# PCIe_LB_bridge.net
KiCad netlist of a schematic drawn in Altium Designer
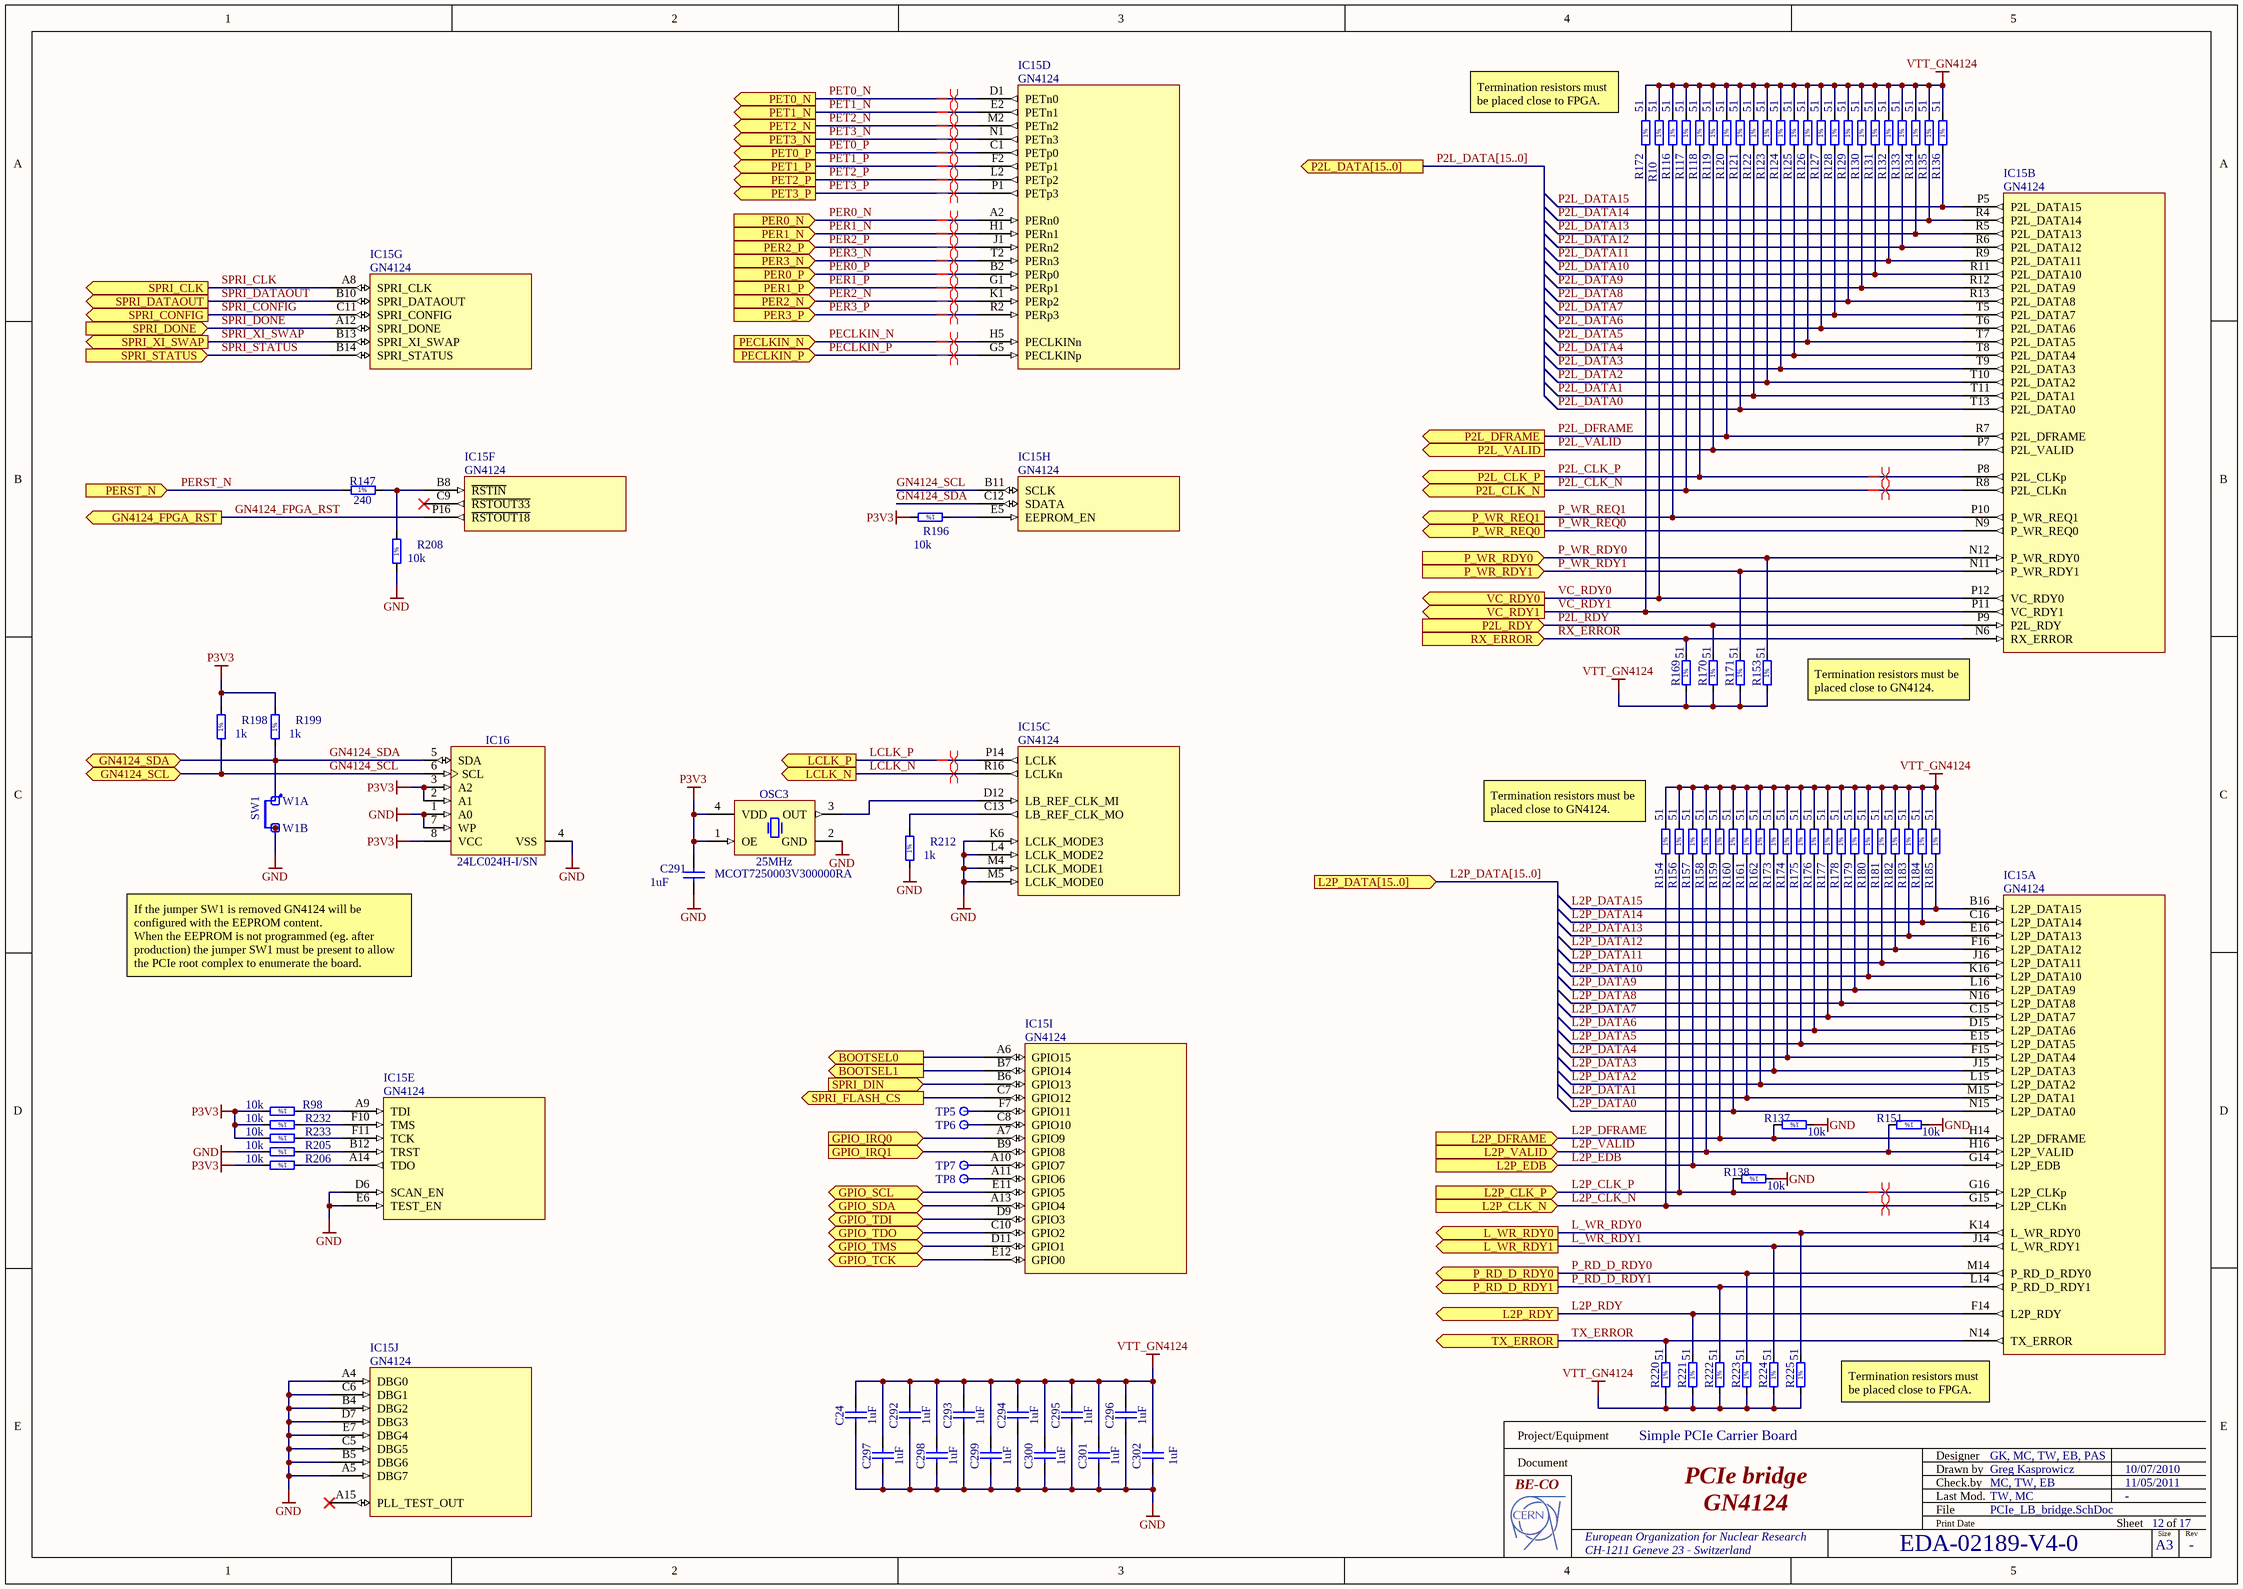
[diagram p0: PCIe_LB_bridge.SchDoc]

(export (version "E")
  (design (tool "Eeschema 10.0.6"))
  (components
    (comp (ref "C24")
      (value "1uF")
      (footprint "CAPC1608X87N")
      (description "Non-polarised capacitor")
      (fields
        (field (name "PART NUMBER") "CC0603_1UF_16V_10%_X7R")
        (field (name "VOLTAGE") "16V")
        (field (name "AUTHOR") "CERN DEM JLC")
      )
      (libsource (lib "Capacitors") (part "Capacitor - non polarized"))
    )
    (comp (ref "C291")
      (value "1uF")
      (footprint "CAPC1608X87N")
      (description "Non-polarised capacitor")
      (fields
        (field (name "PART NUMBER") "CC0603_1UF_16V_10%_X7R")
        (field (name "VOLTAGE") "16V")
        (field (name "AUTHOR") "CERN DEM JLC")
      )
      (libsource (lib "Capacitors") (part "Capacitor - non polarized"))
    )
    (comp (ref "C292")
      (value "1uF")
      (footprint "CAPC1608X87N")
      (description "Non-polarised capacitor")
      (fields
        (field (name "PART NUMBER") "CC0603_1UF_16V_10%_X7R")
        (field (name "VOLTAGE") "16V")
        (field (name "AUTHOR") "CERN DEM JLC")
      )
      (libsource (lib "Capacitors") (part "Capacitor - non polarized"))
    )
    (comp (ref "C293")
      (value "1uF")
      (footprint "CAPC1608X87N")
      (description "Non-polarised capacitor")
      (fields
        (field (name "PART NUMBER") "CC0603_1UF_16V_10%_X7R")
        (field (name "VOLTAGE") "16V")
        (field (name "AUTHOR") "CERN DEM JLC")
      )
      (libsource (lib "Capacitors") (part "Capacitor - non polarized"))
    )
    (comp (ref "C294")
      (value "1uF")
      (footprint "CAPC1608X87N")
      (description "Non-polarised capacitor")
      (fields
        (field (name "PART NUMBER") "CC0603_1UF_16V_10%_X7R")
        (field (name "VOLTAGE") "16V")
        (field (name "AUTHOR") "CERN DEM JLC")
      )
      (libsource (lib "Capacitors") (part "Capacitor - non polarized"))
    )
    (comp (ref "C295")
      (value "1uF")
      (footprint "CAPC1608X87N")
      (description "Non-polarised capacitor")
      (fields
        (field (name "PART NUMBER") "CC0603_1UF_16V_10%_X7R")
        (field (name "VOLTAGE") "16V")
        (field (name "AUTHOR") "CERN DEM JLC")
      )
      (libsource (lib "Capacitors") (part "Capacitor - non polarized"))
    )
    (comp (ref "C296")
      (value "1uF")
      (footprint "CAPC1608X87N")
      (description "Non-polarised capacitor")
      (fields
        (field (name "PART NUMBER") "CC0603_1UF_16V_10%_X7R")
        (field (name "VOLTAGE") "16V")
        (field (name "AUTHOR") "CERN DEM JLC")
      )
      (libsource (lib "Capacitors") (part "Capacitor - non polarized"))
    )
    (comp (ref "C297")
      (value "1uF")
      (footprint "CAPC1608X87N")
      (description "Non-polarised capacitor")
      (fields
        (field (name "PART NUMBER") "CC0603_1UF_16V_10%_X7R")
        (field (name "VOLTAGE") "16V")
        (field (name "AUTHOR") "CERN DEM JLC")
      )
      (libsource (lib "Capacitors") (part "Capacitor - non polarized"))
    )
    (comp (ref "C298")
      (value "1uF")
      (footprint "CAPC1608X87N")
      (description "Non-polarised capacitor")
      (fields
        (field (name "PART NUMBER") "CC0603_1UF_16V_10%_X7R")
        (field (name "VOLTAGE") "16V")
        (field (name "AUTHOR") "CERN DEM JLC")
      )
      (libsource (lib "Capacitors") (part "Capacitor - non polarized"))
    )
    (comp (ref "C299")
      (value "1uF")
      (footprint "CAPC1608X87N")
      (description "Non-polarised capacitor")
      (fields
        (field (name "PART NUMBER") "CC0603_1UF_16V_10%_X7R")
        (field (name "VOLTAGE") "16V")
        (field (name "AUTHOR") "CERN DEM JLC")
      )
      (libsource (lib "Capacitors") (part "Capacitor - non polarized"))
    )
    (comp (ref "C300")
      (value "1uF")
      (footprint "CAPC1608X87N")
      (description "Non-polarised capacitor")
      (fields
        (field (name "PART NUMBER") "CC0603_1UF_16V_10%_X7R")
        (field (name "VOLTAGE") "16V")
        (field (name "AUTHOR") "CERN DEM JLC")
      )
      (libsource (lib "Capacitors") (part "Capacitor - non polarized"))
    )
    (comp (ref "C301")
      (value "1uF")
      (footprint "CAPC1608X87N")
      (description "Non-polarised capacitor")
      (fields
        (field (name "PART NUMBER") "CC0603_1UF_16V_10%_X7R")
        (field (name "VOLTAGE") "16V")
        (field (name "AUTHOR") "CERN DEM JLC")
      )
      (libsource (lib "Capacitors") (part "Capacitor - non polarized"))
    )
    (comp (ref "C302")
      (value "1uF")
      (footprint "CAPC1608X87N")
      (description "Non-polarised capacitor")
      (fields
        (field (name "PART NUMBER") "CC0603_1UF_16V_10%_X7R")
        (field (name "VOLTAGE") "16V")
        (field (name "AUTHOR") "CERN DEM JLC")
      )
      (libsource (lib "Capacitors") (part "Capacitor - non polarized"))
    )
    (comp (ref "IC15")
      (value "GN4124")
      (footprint "BGA256C100P16X16_1700X1700X150")
      (description "x4 Lane PCI Express to Local Bridge")
      (fields (field (name "MANUFACTURER") "GENNUM") (field (name "AUTHOR") "CERN DEM JLC"))
      (libsource (lib "ICs And Semiconductors") (part "GN4124"))
    )
    (comp (ref "IC16")
      (value "24LC024H-I/SN")
      (footprint "SOIC127P600X175-8N")
      (description "2K I2C Serial EEPROM With Half-Array Write Protect")
      (fields (field (name "MANUFACTURER") "MICROCHIP TECHNOLOGY") (field (name "AUTHOR") "CERN DEM JLC"))
      (libsource (lib "ICs And Semiconductors") (part "24LC024H-I/SN"))
    )
    (comp (ref "OSC3")
      (value "25MHz")
      (footprint "OSCSC508P500X700X160-4N")
      (description "Oscillator 4 pins 1=OE 2=GND 3=OUT 4=VDD")
      (fields
        (field (name "PART NUMBER") "OSC_25MHZ_MULTICOMP_MCOT7250003V300000RA")
        (field (name "MANUFACTURER") "MULTICOMP")
        (field (name "MANUFACTURER PART NUMBER") "MCOT7250003V300000RA")
        (field (name "AUTHOR") "CERN DEM JLC")
      )
      (libsource (lib "ICs And Semiconductors") (part "Oscillator 1OE 2GND 3OUT 4VDD"))
    )
    (comp (ref "R10")
      (value "51")
      (footprint "RESC1005X40N")
      (description "Resistor - 1%")
      (fields
        (field (name "PART NUMBER") "R0402_51R_1%_0.0625W_100PPM")
        (field (name "POWER") "0.0625W")
        (field (name "AUTHOR") "CERN DEM JLC")
      )
      (libsource (lib "Resistors") (part "Resistor - 1%"))
    )
    (comp (ref "R98")
      (value "10k")
      (footprint "RESC1608X55N")
      (description "Resistor - 1%")
      (fields
        (field (name "PART NUMBER") "R0603_10K_1%_0.1W_100PPM")
        (field (name "POWER") "0.1W")
        (field (name "AUTHOR") "CERN DEM JLC")
      )
      (libsource (lib "Resistors") (part "Resistor - 1%"))
    )
    (comp (ref "R116")
      (value "51")
      (footprint "RESC1005X40N")
      (description "Resistor - 1%")
      (fields
        (field (name "PART NUMBER") "R0402_51R_1%_0.0625W_100PPM")
        (field (name "POWER") "0.0625W")
        (field (name "AUTHOR") "CERN DEM JLC")
      )
      (libsource (lib "Resistors") (part "Resistor - 1%"))
    )
    (comp (ref "R117")
      (value "51")
      (footprint "RESC1005X40N")
      (description "Resistor - 1%")
      (fields
        (field (name "PART NUMBER") "R0402_51R_1%_0.0625W_100PPM")
        (field (name "POWER") "0.0625W")
        (field (name "AUTHOR") "CERN DEM JLC")
      )
      (libsource (lib "Resistors") (part "Resistor - 1%"))
    )
    (comp (ref "R118")
      (value "51")
      (footprint "RESC1005X40N")
      (description "Resistor - 1%")
      (fields
        (field (name "PART NUMBER") "R0402_51R_1%_0.0625W_100PPM")
        (field (name "POWER") "0.0625W")
        (field (name "AUTHOR") "CERN DEM JLC")
      )
      (libsource (lib "Resistors") (part "Resistor - 1%"))
    )
    (comp (ref "R119")
      (value "51")
      (footprint "RESC1005X40N")
      (description "Resistor - 1%")
      (fields
        (field (name "PART NUMBER") "R0402_51R_1%_0.0625W_100PPM")
        (field (name "POWER") "0.0625W")
        (field (name "AUTHOR") "CERN DEM JLC")
      )
      (libsource (lib "Resistors") (part "Resistor - 1%"))
    )
    (comp (ref "R120")
      (value "51")
      (footprint "RESC1005X40N")
      (description "Resistor - 1%")
      (fields
        (field (name "PART NUMBER") "R0402_51R_1%_0.0625W_100PPM")
        (field (name "POWER") "0.0625W")
        (field (name "AUTHOR") "CERN DEM JLC")
      )
      (libsource (lib "Resistors") (part "Resistor - 1%"))
    )
    (comp (ref "R121")
      (value "51")
      (footprint "RESC1005X40N")
      (description "Resistor - 1%")
      (fields
        (field (name "PART NUMBER") "R0402_51R_1%_0.0625W_100PPM")
        (field (name "POWER") "0.0625W")
        (field (name "AUTHOR") "CERN DEM JLC")
      )
      (libsource (lib "Resistors") (part "Resistor - 1%"))
    )
    (comp (ref "R122")
      (value "51")
      (footprint "RESC1005X40N")
      (description "Resistor - 1%")
      (fields
        (field (name "PART NUMBER") "R0402_51R_1%_0.0625W_100PPM")
        (field (name "POWER") "0.0625W")
        (field (name "AUTHOR") "CERN DEM JLC")
      )
      (libsource (lib "Resistors") (part "Resistor - 1%"))
    )
    (comp (ref "R123")
      (value "51")
      (footprint "RESC1005X40N")
      (description "Resistor - 1%")
      (fields
        (field (name "PART NUMBER") "R0402_51R_1%_0.0625W_100PPM")
        (field (name "POWER") "0.0625W")
        (field (name "AUTHOR") "CERN DEM JLC")
      )
      (libsource (lib "Resistors") (part "Resistor - 1%"))
    )
    (comp (ref "R124")
      (value "51")
      (footprint "RESC1005X40N")
      (description "Resistor - 1%")
      (fields
        (field (name "PART NUMBER") "R0402_51R_1%_0.0625W_100PPM")
        (field (name "POWER") "0.0625W")
        (field (name "AUTHOR") "CERN DEM JLC")
      )
      (libsource (lib "Resistors") (part "Resistor - 1%"))
    )
    (comp (ref "R125")
      (value "51")
      (footprint "RESC1005X40N")
      (description "Resistor - 1%")
      (fields
        (field (name "PART NUMBER") "R0402_51R_1%_0.0625W_100PPM")
        (field (name "POWER") "0.0625W")
        (field (name "AUTHOR") "CERN DEM JLC")
      )
      (libsource (lib "Resistors") (part "Resistor - 1%"))
    )
    (comp (ref "R126")
      (value "51")
      (footprint "RESC1005X40N")
      (description "Resistor - 1%")
      (fields
        (field (name "PART NUMBER") "R0402_51R_1%_0.0625W_100PPM")
        (field (name "POWER") "0.0625W")
        (field (name "AUTHOR") "CERN DEM JLC")
      )
      (libsource (lib "Resistors") (part "Resistor - 1%"))
    )
    (comp (ref "R127")
      (value "51")
      (footprint "RESC1005X40N")
      (description "Resistor - 1%")
      (fields
        (field (name "PART NUMBER") "R0402_51R_1%_0.0625W_100PPM")
        (field (name "POWER") "0.0625W")
        (field (name "AUTHOR") "CERN DEM JLC")
      )
      (libsource (lib "Resistors") (part "Resistor - 1%"))
    )
    (comp (ref "R128")
      (value "51")
      (footprint "RESC1005X40N")
      (description "Resistor - 1%")
      (fields
        (field (name "PART NUMBER") "R0402_51R_1%_0.0625W_100PPM")
        (field (name "POWER") "0.0625W")
        (field (name "AUTHOR") "CERN DEM JLC")
      )
      (libsource (lib "Resistors") (part "Resistor - 1%"))
    )
    (comp (ref "R129")
      (value "51")
      (footprint "RESC1005X40N")
      (description "Resistor - 1%")
      (fields
        (field (name "PART NUMBER") "R0402_51R_1%_0.0625W_100PPM")
        (field (name "POWER") "0.0625W")
        (field (name "AUTHOR") "CERN DEM JLC")
      )
      (libsource (lib "Resistors") (part "Resistor - 1%"))
    )
    (comp (ref "R130")
      (value "51")
      (footprint "RESC1005X40N")
      (description "Resistor - 1%")
      (fields
        (field (name "PART NUMBER") "R0402_51R_1%_0.0625W_100PPM")
        (field (name "POWER") "0.0625W")
        (field (name "AUTHOR") "CERN DEM JLC")
      )
      (libsource (lib "Resistors") (part "Resistor - 1%"))
    )
    (comp (ref "R131")
      (value "51")
      (footprint "RESC1005X40N")
      (description "Resistor - 1%")
      (fields
        (field (name "PART NUMBER") "R0402_51R_1%_0.0625W_100PPM")
        (field (name "POWER") "0.0625W")
        (field (name "AUTHOR") "CERN DEM JLC")
      )
      (libsource (lib "Resistors") (part "Resistor - 1%"))
    )
    (comp (ref "R132")
      (value "51")
      (footprint "RESC1005X40N")
      (description "Resistor - 1%")
      (fields
        (field (name "PART NUMBER") "R0402_51R_1%_0.0625W_100PPM")
        (field (name "POWER") "0.0625W")
        (field (name "AUTHOR") "CERN DEM JLC")
      )
      (libsource (lib "Resistors") (part "Resistor - 1%"))
    )
    (comp (ref "R133")
      (value "51")
      (footprint "RESC1005X40N")
      (description "Resistor - 1%")
      (fields
        (field (name "PART NUMBER") "R0402_51R_1%_0.0625W_100PPM")
        (field (name "POWER") "0.0625W")
        (field (name "AUTHOR") "CERN DEM JLC")
      )
      (libsource (lib "Resistors") (part "Resistor - 1%"))
    )
    (comp (ref "R134")
      (value "51")
      (footprint "RESC1005X40N")
      (description "Resistor - 1%")
      (fields
        (field (name "PART NUMBER") "R0402_51R_1%_0.0625W_100PPM")
        (field (name "POWER") "0.0625W")
        (field (name "AUTHOR") "CERN DEM JLC")
      )
      (libsource (lib "Resistors") (part "Resistor - 1%"))
    )
    (comp (ref "R135")
      (value "51")
      (footprint "RESC1005X40N")
      (description "Resistor - 1%")
      (fields
        (field (name "PART NUMBER") "R0402_51R_1%_0.0625W_100PPM")
        (field (name "POWER") "0.0625W")
        (field (name "AUTHOR") "CERN DEM JLC")
      )
      (libsource (lib "Resistors") (part "Resistor - 1%"))
    )
    (comp (ref "R136")
      (value "51")
      (footprint "RESC1005X40N")
      (description "Resistor - 1%")
      (fields
        (field (name "PART NUMBER") "R0402_51R_1%_0.0625W_100PPM")
        (field (name "POWER") "0.0625W")
        (field (name "AUTHOR") "CERN DEM JLC")
      )
      (libsource (lib "Resistors") (part "Resistor - 1%"))
    )
    (comp (ref "R137")
      (value "10k")
      (footprint "RESC1608X55N")
      (description "Resistor - 1%")
      (fields
        (field (name "PART NUMBER") "R0603_10K_1%_0.1W_100PPM")
        (field (name "POWER") "0.1W")
        (field (name "AUTHOR") "CERN DEM JLC")
      )
      (libsource (lib "Resistors") (part "Resistor - 1%"))
    )
    (comp (ref "R138")
      (value "10k")
      (footprint "RESC1608X55N")
      (description "Resistor - 1%")
      (fields
        (field (name "PART NUMBER") "R0603_10K_1%_0.1W_100PPM")
        (field (name "POWER") "0.1W")
        (field (name "AUTHOR") "CERN DEM JLC")
      )
      (libsource (lib "Resistors") (part "Resistor - 1%"))
    )
    (comp (ref "R147")
      (value "240")
      (footprint "RESC1608X55N")
      (description "Resistor - 1%")
      (fields
        (field (name "PART NUMBER") "R0603_240R_1%_0.1W_100PPM")
        (field (name "POWER") "0.1W")
        (field (name "AUTHOR") "CERN DEM JLC")
      )
      (libsource (lib "Resistors") (part "Resistor - 1%"))
    )
    (comp (ref "R151")
      (value "10k")
      (footprint "RESC1608X55N")
      (description "Resistor - 1%")
      (fields
        (field (name "PART NUMBER") "R0603_10K_1%_0.1W_100PPM")
        (field (name "POWER") "0.1W")
        (field (name "AUTHOR") "CERN DEM JLC")
      )
      (libsource (lib "Resistors") (part "Resistor - 1%"))
    )
    (comp (ref "R153")
      (value "51")
      (footprint "RESC1005X40N")
      (description "Resistor - 1%")
      (fields
        (field (name "PART NUMBER") "R0402_51R_1%_0.0625W_100PPM")
        (field (name "POWER") "0.0625W")
        (field (name "AUTHOR") "CERN DEM JLC")
      )
      (libsource (lib "Resistors") (part "Resistor - 1%"))
    )
    (comp (ref "R154")
      (value "51")
      (footprint "RESC1005X40N")
      (description "Resistor - 1%")
      (fields
        (field (name "PART NUMBER") "R0402_51R_1%_0.0625W_100PPM")
        (field (name "POWER") "0.0625W")
        (field (name "AUTHOR") "CERN DEM JLC")
      )
      (libsource (lib "Resistors") (part "Resistor - 1%"))
    )
    (comp (ref "R156")
      (value "51")
      (footprint "RESC1005X40N")
      (description "Resistor - 1%")
      (fields
        (field (name "PART NUMBER") "R0402_51R_1%_0.0625W_100PPM")
        (field (name "POWER") "0.0625W")
        (field (name "AUTHOR") "CERN DEM JLC")
      )
      (libsource (lib "Resistors") (part "Resistor - 1%"))
    )
    (comp (ref "R157")
      (value "51")
      (footprint "RESC1005X40N")
      (description "Resistor - 1%")
      (fields
        (field (name "PART NUMBER") "R0402_51R_1%_0.0625W_100PPM")
        (field (name "POWER") "0.0625W")
        (field (name "AUTHOR") "CERN DEM JLC")
      )
      (libsource (lib "Resistors") (part "Resistor - 1%"))
    )
    (comp (ref "R158")
      (value "51")
      (footprint "RESC1005X40N")
      (description "Resistor - 1%")
      (fields
        (field (name "PART NUMBER") "R0402_51R_1%_0.0625W_100PPM")
        (field (name "POWER") "0.0625W")
        (field (name "AUTHOR") "CERN DEM JLC")
      )
      (libsource (lib "Resistors") (part "Resistor - 1%"))
    )
    (comp (ref "R159")
      (value "51")
      (footprint "RESC1005X40N")
      (description "Resistor - 1%")
      (fields
        (field (name "PART NUMBER") "R0402_51R_1%_0.0625W_100PPM")
        (field (name "POWER") "0.0625W")
        (field (name "AUTHOR") "CERN DEM JLC")
      )
      (libsource (lib "Resistors") (part "Resistor - 1%"))
    )
    (comp (ref "R160")
      (value "51")
      (footprint "RESC1005X40N")
      (description "Resistor - 1%")
      (fields
        (field (name "PART NUMBER") "R0402_51R_1%_0.0625W_100PPM")
        (field (name "POWER") "0.0625W")
        (field (name "AUTHOR") "CERN DEM JLC")
      )
      (libsource (lib "Resistors") (part "Resistor - 1%"))
    )
    (comp (ref "R161")
      (value "51")
      (footprint "RESC1005X40N")
      (description "Resistor - 1%")
      (fields
        (field (name "PART NUMBER") "R0402_51R_1%_0.0625W_100PPM")
        (field (name "POWER") "0.0625W")
        (field (name "AUTHOR") "CERN DEM JLC")
      )
      (libsource (lib "Resistors") (part "Resistor - 1%"))
    )
    (comp (ref "R162")
      (value "51")
      (footprint "RESC1005X40N")
      (description "Resistor - 1%")
      (fields
        (field (name "PART NUMBER") "R0402_51R_1%_0.0625W_100PPM")
        (field (name "POWER") "0.0625W")
        (field (name "AUTHOR") "CERN DEM JLC")
      )
      (libsource (lib "Resistors") (part "Resistor - 1%"))
    )
    (comp (ref "R169")
      (value "51")
      (footprint "RESC1005X40N")
      (description "Resistor - 1%")
      (fields
        (field (name "PART NUMBER") "R0402_51R_1%_0.0625W_100PPM")
        (field (name "POWER") "0.0625W")
        (field (name "AUTHOR") "CERN DEM JLC")
      )
      (libsource (lib "Resistors") (part "Resistor - 1%"))
    )
    (comp (ref "R170")
      (value "51")
      (footprint "RESC1005X40N")
      (description "Resistor - 1%")
      (fields
        (field (name "PART NUMBER") "R0402_51R_1%_0.0625W_100PPM")
        (field (name "POWER") "0.0625W")
        (field (name "AUTHOR") "CERN DEM JLC")
      )
      (libsource (lib "Resistors") (part "Resistor - 1%"))
    )
    (comp (ref "R171")
      (value "51")
      (footprint "RESC1005X40N")
      (description "Resistor - 1%")
      (fields
        (field (name "PART NUMBER") "R0402_51R_1%_0.0625W_100PPM")
        (field (name "POWER") "0.0625W")
        (field (name "AUTHOR") "CERN DEM JLC")
      )
      (libsource (lib "Resistors") (part "Resistor - 1%"))
    )
    (comp (ref "R172")
      (value "51")
      (footprint "RESC1005X40N")
      (description "Resistor - 1%")
      (fields
        (field (name "PART NUMBER") "R0402_51R_1%_0.0625W_100PPM")
        (field (name "POWER") "0.0625W")
        (field (name "AUTHOR") "CERN DEM JLC")
      )
      (libsource (lib "Resistors") (part "Resistor - 1%"))
    )
    (comp (ref "R173")
      (value "51")
      (footprint "RESC1005X40N")
      (description "Resistor - 1%")
      (fields
        (field (name "PART NUMBER") "R0402_51R_1%_0.0625W_100PPM")
        (field (name "POWER") "0.0625W")
        (field (name "AUTHOR") "CERN DEM JLC")
      )
      (libsource (lib "Resistors") (part "Resistor - 1%"))
    )
    (comp (ref "R174")
      (value "51")
      (footprint "RESC1005X40N")
      (description "Resistor - 1%")
      (fields
        (field (name "PART NUMBER") "R0402_51R_1%_0.0625W_100PPM")
        (field (name "POWER") "0.0625W")
        (field (name "AUTHOR") "CERN DEM JLC")
      )
      (libsource (lib "Resistors") (part "Resistor - 1%"))
    )
    (comp (ref "R175")
      (value "51")
      (footprint "RESC1005X40N")
      (description "Resistor - 1%")
      (fields
        (field (name "PART NUMBER") "R0402_51R_1%_0.0625W_100PPM")
        (field (name "POWER") "0.0625W")
        (field (name "AUTHOR") "CERN DEM JLC")
      )
      (libsource (lib "Resistors") (part "Resistor - 1%"))
    )
    (comp (ref "R176")
      (value "51")
      (footprint "RESC1005X40N")
      (description "Resistor - 1%")
      (fields
        (field (name "PART NUMBER") "R0402_51R_1%_0.0625W_100PPM")
        (field (name "POWER") "0.0625W")
        (field (name "AUTHOR") "CERN DEM JLC")
      )
      (libsource (lib "Resistors") (part "Resistor - 1%"))
    )
    (comp (ref "R177")
      (value "51")
      (footprint "RESC1005X40N")
      (description "Resistor - 1%")
      (fields
        (field (name "PART NUMBER") "R0402_51R_1%_0.0625W_100PPM")
        (field (name "POWER") "0.0625W")
        (field (name "AUTHOR") "CERN DEM JLC")
      )
      (libsource (lib "Resistors") (part "Resistor - 1%"))
    )
    (comp (ref "R178")
      (value "51")
      (footprint "RESC1005X40N")
      (description "Resistor - 1%")
      (fields
        (field (name "PART NUMBER") "R0402_51R_1%_0.0625W_100PPM")
        (field (name "POWER") "0.0625W")
        (field (name "AUTHOR") "CERN DEM JLC")
      )
      (libsource (lib "Resistors") (part "Resistor - 1%"))
    )
    (comp (ref "R179")
      (value "51")
      (footprint "RESC1005X40N")
      (description "Resistor - 1%")
      (fields
        (field (name "PART NUMBER") "R0402_51R_1%_0.0625W_100PPM")
        (field (name "POWER") "0.0625W")
        (field (name "AUTHOR") "CERN DEM JLC")
      )
      (libsource (lib "Resistors") (part "Resistor - 1%"))
    )
    (comp (ref "R180")
      (value "51")
      (footprint "RESC1005X40N")
      (description "Resistor - 1%")
      (fields
        (field (name "PART NUMBER") "R0402_51R_1%_0.0625W_100PPM")
        (field (name "POWER") "0.0625W")
        (field (name "AUTHOR") "CERN DEM JLC")
      )
      (libsource (lib "Resistors") (part "Resistor - 1%"))
    )
    (comp (ref "R181")
      (value "51")
      (footprint "RESC1005X40N")
      (description "Resistor - 1%")
      (fields
        (field (name "PART NUMBER") "R0402_51R_1%_0.0625W_100PPM")
        (field (name "POWER") "0.0625W")
        (field (name "AUTHOR") "CERN DEM JLC")
      )
      (libsource (lib "Resistors") (part "Resistor - 1%"))
    )
    (comp (ref "R182")
      (value "51")
      (footprint "RESC1005X40N")
      (description "Resistor - 1%")
      (fields
        (field (name "PART NUMBER") "R0402_51R_1%_0.0625W_100PPM")
        (field (name "POWER") "0.0625W")
        (field (name "AUTHOR") "CERN DEM JLC")
      )
      (libsource (lib "Resistors") (part "Resistor - 1%"))
    )
    (comp (ref "R183")
      (value "51")
      (footprint "RESC1005X40N")
      (description "Resistor - 1%")
      (fields
        (field (name "PART NUMBER") "R0402_51R_1%_0.0625W_100PPM")
        (field (name "POWER") "0.0625W")
        (field (name "AUTHOR") "CERN DEM JLC")
      )
      (libsource (lib "Resistors") (part "Resistor - 1%"))
    )
    (comp (ref "R184")
      (value "51")
      (footprint "RESC1005X40N")
      (description "Resistor - 1%")
      (fields
        (field (name "PART NUMBER") "R0402_51R_1%_0.0625W_100PPM")
        (field (name "POWER") "0.0625W")
        (field (name "AUTHOR") "CERN DEM JLC")
      )
      (libsource (lib "Resistors") (part "Resistor - 1%"))
    )
    (comp (ref "R185")
      (value "51")
      (footprint "RESC1005X40N")
      (description "Resistor - 1%")
      (fields
        (field (name "PART NUMBER") "R0402_51R_1%_0.0625W_100PPM")
        (field (name "POWER") "0.0625W")
        (field (name "AUTHOR") "CERN DEM JLC")
      )
      (libsource (lib "Resistors") (part "Resistor - 1%"))
    )
    (comp (ref "R196")
      (value "10k")
      (footprint "RESC1608X55N")
      (description "Resistor - 1%")
      (fields
        (field (name "PART NUMBER") "R0603_10K_1%_0.1W_100PPM")
        (field (name "POWER") "0.1W")
        (field (name "AUTHOR") "CERN DEM JLC")
      )
      (libsource (lib "Resistors") (part "Resistor - 1%"))
    )
    (comp (ref "R198")
      (value "1k")
      (footprint "RESC1608X55N")
      (description "Resistor - 1%")
      (fields
        (field (name "PART NUMBER") "R0603_1K_1%_0.1W_100PPM")
        (field (name "POWER") "0.1W")
        (field (name "AUTHOR") "CERN DEM JLC")
      )
      (libsource (lib "Resistors") (part "Resistor - 1%"))
    )
    (comp (ref "R199")
      (value "1k")
      (footprint "RESC1608X55N")
      (description "Resistor - 1%")
      (fields
        (field (name "PART NUMBER") "R0603_1K_1%_0.1W_100PPM")
        (field (name "POWER") "0.1W")
        (field (name "AUTHOR") "CERN DEM JLC")
      )
      (libsource (lib "Resistors") (part "Resistor - 1%"))
    )
    (comp (ref "R205")
      (value "10k")
      (footprint "RESC1608X55N")
      (description "Resistor - 1%")
      (fields
        (field (name "PART NUMBER") "R0603_10K_1%_0.1W_100PPM")
        (field (name "POWER") "0.1W")
        (field (name "AUTHOR") "CERN DEM JLC")
      )
      (libsource (lib "Resistors") (part "Resistor - 1%"))
    )
    (comp (ref "R206")
      (value "10k")
      (footprint "RESC1608X55N")
      (description "Resistor - 1%")
      (fields
        (field (name "PART NUMBER") "R0603_10K_1%_0.1W_100PPM")
        (field (name "POWER") "0.1W")
        (field (name "AUTHOR") "CERN DEM JLC")
      )
      (libsource (lib "Resistors") (part "Resistor - 1%"))
    )
    (comp (ref "R208")
      (value "10k")
      (footprint "RESC1608X55N")
      (description "Resistor - 1%")
      (fields
        (field (name "PART NUMBER") "R0603_10K_1%_0.1W_100PPM")
        (field (name "POWER") "0.1W")
        (field (name "AUTHOR") "CERN DEM JLC")
      )
      (libsource (lib "Resistors") (part "Resistor - 1%"))
    )
    (comp (ref "R212")
      (value "1k")
      (footprint "RESC1608X55N")
      (description "Resistor - 1%")
      (fields
        (field (name "PART NUMBER") "R0603_1K_1%_0.1W_100PPM")
        (field (name "POWER") "0.1W")
        (field (name "AUTHOR") "CERN DEM JLC")
      )
      (libsource (lib "Resistors") (part "Resistor - 1%"))
    )
    (comp (ref "R220")
      (value "51")
      (footprint "RESC1005X40N")
      (description "Resistor - 1%")
      (fields
        (field (name "PART NUMBER") "R0402_51R_1%_0.0625W_100PPM")
        (field (name "POWER") "0.0625W")
        (field (name "AUTHOR") "CERN DEM JLC")
      )
      (libsource (lib "Resistors") (part "Resistor - 1%"))
    )
    (comp (ref "R221")
      (value "51")
      (footprint "RESC1005X40N")
      (description "Resistor - 1%")
      (fields
        (field (name "PART NUMBER") "R0402_51R_1%_0.0625W_100PPM")
        (field (name "POWER") "0.0625W")
        (field (name "AUTHOR") "CERN DEM JLC")
      )
      (libsource (lib "Resistors") (part "Resistor - 1%"))
    )
    (comp (ref "R222")
      (value "51")
      (footprint "RESC1005X40N")
      (description "Resistor - 1%")
      (fields
        (field (name "PART NUMBER") "R0402_51R_1%_0.0625W_100PPM")
        (field (name "POWER") "0.0625W")
        (field (name "AUTHOR") "CERN DEM JLC")
      )
      (libsource (lib "Resistors") (part "Resistor - 1%"))
    )
    (comp (ref "R223")
      (value "51")
      (footprint "RESC1005X40N")
      (description "Resistor - 1%")
      (fields
        (field (name "PART NUMBER") "R0402_51R_1%_0.0625W_100PPM")
        (field (name "POWER") "0.0625W")
        (field (name "AUTHOR") "CERN DEM JLC")
      )
      (libsource (lib "Resistors") (part "Resistor - 1%"))
    )
    (comp (ref "R224")
      (value "51")
      (footprint "RESC1005X40N")
      (description "Resistor - 1%")
      (fields
        (field (name "PART NUMBER") "R0402_51R_1%_0.0625W_100PPM")
        (field (name "POWER") "0.0625W")
        (field (name "AUTHOR") "CERN DEM JLC")
      )
      (libsource (lib "Resistors") (part "Resistor - 1%"))
    )
    (comp (ref "R225")
      (value "51")
      (footprint "RESC1005X40N")
      (description "Resistor - 1%")
      (fields
        (field (name "PART NUMBER") "R0402_51R_1%_0.0625W_100PPM")
        (field (name "POWER") "0.0625W")
        (field (name "AUTHOR") "CERN DEM JLC")
      )
      (libsource (lib "Resistors") (part "Resistor - 1%"))
    )
    (comp (ref "R232")
      (value "10k")
      (footprint "RESC1608X55N")
      (description "Resistor - 1%")
      (fields
        (field (name "PART NUMBER") "R0603_10K_1%_0.1W_100PPM")
        (field (name "POWER") "0.1W")
        (field (name "AUTHOR") "CERN DEM JLC")
      )
      (libsource (lib "Resistors") (part "Resistor - 1%"))
    )
    (comp (ref "R233")
      (value "10k")
      (footprint "RESC1608X55N")
      (description "Resistor - 1%")
      (fields
        (field (name "PART NUMBER") "R0603_10K_1%_0.1W_100PPM")
        (field (name "POWER") "0.1W")
        (field (name "AUTHOR") "CERN DEM JLC")
      )
      (libsource (lib "Resistors") (part "Resistor - 1%"))
    )
    (comp (ref "SW1")
      (value "Jumper Type1")
      (footprint "JUMPER_BLACK_INSULATED_2.54MM")
      (description "Jumper 1 Pin")
      (fields
        (field (name "PART NUMBER") "COMATEL_313.1730.0.00.40.0")
        (field (name "MANUFACTURER") "KONTEK COMATEL")
        (field (name "AUTHOR") "CERN DEM JLC")
      )
      (libsource (lib "Connectors") (part "Jumper Type1"))
    )
    (comp (ref "TP5")
      (value "Test Point")
      (footprint "TPS127")
      (fields (field (name "PART NUMBER") "SMD_PAD_1.27X1.27MM") (field (name "AUTHOR") "CERN DEM JLC"))
      (libsource (lib "Eletro-mechanical") (part "Test Point"))
    )
    (comp (ref "TP6")
      (value "Test Point")
      (footprint "TPS127")
      (fields (field (name "PART NUMBER") "SMD_PAD_1.27X1.27MM") (field (name "AUTHOR") "CERN DEM JLC"))
      (libsource (lib "Eletro-mechanical") (part "Test Point"))
    )
    (comp (ref "TP7")
      (value "Test Point")
      (footprint "TPS127")
      (fields (field (name "PART NUMBER") "SMD_PAD_1.27X1.27MM") (field (name "AUTHOR") "CERN DEM JLC"))
      (libsource (lib "Eletro-mechanical") (part "Test Point"))
    )
    (comp (ref "TP8")
      (value "Test Point")
      (footprint "TPS127")
      (fields (field (name "PART NUMBER") "SMD_PAD_1.27X1.27MM") (field (name "AUTHOR") "CERN DEM JLC"))
      (libsource (lib "Eletro-mechanical") (part "Test Point"))
    )
    (comp (ref "W1")
      (value "Header 2")
      (footprint "HARWIN_M20-9990246")
      (description "2 Mini Wire-Wrap Contact Strip Header")
      (fields
        (field (name "PART NUMBER") "HARWIN_M20-9990246")
        (field (name "MANUFACTURER") "HARWIN")
        (field (name "AUTHOR") "CERN DEM JLC")
      )
      (libsource (lib "Connectors") (part "Wire-Wrap Contact x2"))
    )
  )
  (nets
    (net (code "1") (name "/BOOTSEL0") (class "Default")
      (node (ref "IC15") (pin "A6") (pinfunction "GPIO15_A6") (pintype "bidirectional"))
    )
    (net (code "2") (name "/BOOTSEL1") (class "Default")
      (node (ref "IC15") (pin "B7") (pinfunction "GPIO14_B7") (pintype "bidirectional"))
    )
    (net (code "3") (name "/GN4124_FPGA_RST") (class "Default")
      (node (ref "IC15") (pin "P16") (pinfunction "RSTOUT18_P16") (pintype "output"))
    )
    (net (code "4") (name "/GN4124_SCL") (class "Default")
      (node (ref "IC15") (pin "B11") (pinfunction "SCLK_B11") (pintype "bidirectional"))
      (node (ref "IC16") (pin "6") (pinfunction "SCL_6") (pintype "input"))
      (node (ref "R198") (pin "1") (pinfunction "1_1") (pintype "passive"))
    )
    (net (code "5") (name "/GN4124_SDA") (class "Default")
      (node (ref "IC15") (pin "C12") (pinfunction "SDATA_C12") (pintype "bidirectional"))
      (node (ref "IC16") (pin "5") (pinfunction "SDA_5") (pintype "bidirectional"))
      (node (ref "R199") (pin "1") (pinfunction "1_1") (pintype "passive"))
      (node (ref "W1") (pin "1") (pinfunction "1_1") (pintype "bidirectional"))
    )
    (net (code "6") (name "/GPIO_IRQ0") (class "Default")
      (node (ref "IC15") (pin "A7") (pinfunction "GPIO9_A7") (pintype "bidirectional"))
    )
    (net (code "7") (name "/GPIO_IRQ1") (class "Default")
      (node (ref "IC15") (pin "B9") (pinfunction "GPIO8_B9") (pintype "bidirectional"))
    )
    (net (code "8") (name "/GPIO_SCL") (class "Default")
      (node (ref "IC15") (pin "E11") (pinfunction "GPIO5_E11") (pintype "bidirectional"))
    )
    (net (code "9") (name "/GPIO_SDA") (class "Default")
      (node (ref "IC15") (pin "A13") (pinfunction "GPIO4_A13") (pintype "bidirectional"))
    )
    (net (code "10") (name "/GPIO_TCK") (class "Default")
      (node (ref "IC15") (pin "E12") (pinfunction "GPIO0_E12") (pintype "bidirectional"))
    )
    (net (code "11") (name "/GPIO_TDI") (class "Default")
      (node (ref "IC15") (pin "D9") (pinfunction "GPIO3_D9") (pintype "bidirectional"))
    )
    (net (code "12") (name "/GPIO_TDO") (class "Default")
      (node (ref "IC15") (pin "C10") (pinfunction "GPIO2_C10") (pintype "bidirectional"))
    )
    (net (code "13") (name "/GPIO_TMS") (class "Default")
      (node (ref "IC15") (pin "D11") (pinfunction "GPIO1_D11") (pintype "bidirectional"))
    )
    (net (code "14") (name "/L2P_CLK_N") (class "Default")
      (node (ref "IC15") (pin "G15") (pinfunction "L2P_CLKn_G15") (pintype "input"))
      (node (ref "R154") (pin "1") (pinfunction "1_1") (pintype "passive"))
    )
    (net (code "15") (name "/L2P_CLK_P") (class "Default")
      (node (ref "IC15") (pin "G16") (pinfunction "L2P_CLKp_G16") (pintype "input"))
      (node (ref "R138") (pin "2") (pinfunction "2_2") (pintype "passive"))
      (node (ref "R156") (pin "1") (pinfunction "1_1") (pintype "passive"))
    )
    (net (code "16") (name "/L2P_DATA0") (class "Default")
      (node (ref "IC15") (pin "N15") (pinfunction "L2P_DATA0_N15") (pintype "input"))
      (node (ref "R160") (pin "1") (pinfunction "1_1") (pintype "passive"))
    )
    (net (code "17") (name "/L2P_DATA1") (class "Default")
      (node (ref "IC15") (pin "M15") (pinfunction "L2P_DATA1_M15") (pintype "input"))
      (node (ref "R161") (pin "1") (pinfunction "1_1") (pintype "passive"))
    )
    (net (code "18") (name "/L2P_DATA2") (class "Default")
      (node (ref "IC15") (pin "L15") (pinfunction "L2P_DATA2_L15") (pintype "input"))
      (node (ref "R162") (pin "1") (pinfunction "1_1") (pintype "passive"))
    )
    (net (code "19") (name "/L2P_DATA3") (class "Default")
      (node (ref "IC15") (pin "J15") (pinfunction "L2P_DATA3_J15") (pintype "input"))
      (node (ref "R173") (pin "1") (pinfunction "1_1") (pintype "passive"))
    )
    (net (code "20") (name "/L2P_DATA4") (class "Default")
      (node (ref "IC15") (pin "F15") (pinfunction "L2P_DATA4_F15") (pintype "input"))
      (node (ref "R174") (pin "1") (pinfunction "1_1") (pintype "passive"))
    )
    (net (code "21") (name "/L2P_DATA5") (class "Default")
      (node (ref "IC15") (pin "E15") (pinfunction "L2P_DATA5_E15") (pintype "input"))
      (node (ref "R175") (pin "1") (pinfunction "1_1") (pintype "passive"))
    )
    (net (code "22") (name "/L2P_DATA6") (class "Default")
      (node (ref "IC15") (pin "D15") (pinfunction "L2P_DATA6_D15") (pintype "input"))
      (node (ref "R176") (pin "1") (pinfunction "1_1") (pintype "passive"))
    )
    (net (code "23") (name "/L2P_DATA7") (class "Default")
      (node (ref "IC15") (pin "C15") (pinfunction "L2P_DATA7_C15") (pintype "input"))
      (node (ref "R177") (pin "1") (pinfunction "1_1") (pintype "passive"))
    )
    (net (code "24") (name "/L2P_DATA8") (class "Default")
      (node (ref "IC15") (pin "N16") (pinfunction "L2P_DATA8_N16") (pintype "input"))
      (node (ref "R178") (pin "1") (pinfunction "1_1") (pintype "passive"))
    )
    (net (code "25") (name "/L2P_DATA9") (class "Default")
      (node (ref "IC15") (pin "L16") (pinfunction "L2P_DATA9_L16") (pintype "input"))
      (node (ref "R179") (pin "1") (pinfunction "1_1") (pintype "passive"))
    )
    (net (code "26") (name "/L2P_DATA10") (class "Default")
      (node (ref "IC15") (pin "K16") (pinfunction "L2P_DATA10_K16") (pintype "input"))
      (node (ref "R180") (pin "1") (pinfunction "1_1") (pintype "passive"))
    )
    (net (code "27") (name "/L2P_DATA11") (class "Default")
      (node (ref "IC15") (pin "J16") (pinfunction "L2P_DATA11_J16") (pintype "input"))
      (node (ref "R181") (pin "1") (pinfunction "1_1") (pintype "passive"))
    )
    (net (code "28") (name "/L2P_DATA12") (class "Default")
      (node (ref "IC15") (pin "F16") (pinfunction "L2P_DATA12_F16") (pintype "input"))
      (node (ref "R182") (pin "1") (pinfunction "1_1") (pintype "passive"))
    )
    (net (code "29") (name "/L2P_DATA13") (class "Default")
      (node (ref "IC15") (pin "E16") (pinfunction "L2P_DATA13_E16") (pintype "input"))
      (node (ref "R183") (pin "1") (pinfunction "1_1") (pintype "passive"))
    )
    (net (code "30") (name "/L2P_DATA14") (class "Default")
      (node (ref "IC15") (pin "C16") (pinfunction "L2P_DATA14_C16") (pintype "input"))
      (node (ref "R184") (pin "1") (pinfunction "1_1") (pintype "passive"))
    )
    (net (code "31") (name "/L2P_DATA15") (class "Default")
      (node (ref "IC15") (pin "B16") (pinfunction "L2P_DATA15_B16") (pintype "input"))
      (node (ref "R185") (pin "1") (pinfunction "1_1") (pintype "passive"))
    )
    (net (code "33") (name "/L2P_DFRAME") (class "Default")
      (node (ref "IC15") (pin "H14") (pinfunction "L2P_DFRAME_H14") (pintype "input"))
      (node (ref "R137") (pin "2") (pinfunction "2_2") (pintype "passive"))
      (node (ref "R159") (pin "1") (pinfunction "1_1") (pintype "passive"))
    )
    (net (code "34") (name "/L2P_EDB") (class "Default")
      (node (ref "IC15") (pin "G14") (pinfunction "L2P_EDB_G14") (pintype "input"))
      (node (ref "R157") (pin "1") (pinfunction "1_1") (pintype "passive"))
    )
    (net (code "35") (name "/L2P_RDY") (class "Default")
      (node (ref "IC15") (pin "F14") (pinfunction "L2P_RDY_F14") (pintype "output"))
      (node (ref "R221") (pin "2") (pinfunction "2_2") (pintype "passive"))
    )
    (net (code "36") (name "/L2P_VALID") (class "Default")
      (node (ref "IC15") (pin "H16") (pinfunction "L2P_VALID_H16") (pintype "input"))
      (node (ref "R151") (pin "2") (pinfunction "2_2") (pintype "passive"))
      (node (ref "R158") (pin "1") (pinfunction "1_1") (pintype "passive"))
    )
    (net (code "37") (name "/LCLK_N") (class "Default")
      (node (ref "IC15") (pin "R16") (pinfunction "LCLKn_R16") (pintype "output"))
    )
    (net (code "38") (name "/LCLK_P") (class "Default")
      (node (ref "IC15") (pin "P14") (pinfunction "LCLK_P14") (pintype "output"))
    )
    (net (code "39") (name "/L_WR_RDY0") (class "Default")
      (node (ref "IC15") (pin "K14") (pinfunction "L_WR_RDY0_K14") (pintype "output"))
      (node (ref "R225") (pin "2") (pinfunction "2_2") (pintype "passive"))
    )
    (net (code "40") (name "/L_WR_RDY1") (class "Default")
      (node (ref "IC15") (pin "J14") (pinfunction "L_WR_RDY1_J14") (pintype "output"))
      (node (ref "R224") (pin "2") (pinfunction "2_2") (pintype "passive"))
    )
    (net (code "41") (name "/P2L_CLK_N") (class "Default")
      (node (ref "IC15") (pin "R8") (pinfunction "P2L_CLKn_R8") (pintype "output"))
      (node (ref "R117") (pin "1") (pinfunction "1_1") (pintype "passive"))
    )
    (net (code "42") (name "/P2L_CLK_P") (class "Default")
      (node (ref "IC15") (pin "P8") (pinfunction "P2L_CLKp_P8") (pintype "output"))
      (node (ref "R118") (pin "1") (pinfunction "1_1") (pintype "passive"))
    )
    (net (code "43") (name "/P2L_DATA0") (class "Default")
      (node (ref "IC15") (pin "T13") (pinfunction "P2L_DATA0_T13") (pintype "output"))
      (node (ref "R121") (pin "1") (pinfunction "1_1") (pintype "passive"))
    )
    (net (code "44") (name "/P2L_DATA1") (class "Default")
      (node (ref "IC15") (pin "T11") (pinfunction "P2L_DATA1_T11") (pintype "output"))
      (node (ref "R122") (pin "1") (pinfunction "1_1") (pintype "passive"))
    )
    (net (code "45") (name "/P2L_DATA2") (class "Default")
      (node (ref "IC15") (pin "T10") (pinfunction "P2L_DATA2_T10") (pintype "output"))
      (node (ref "R123") (pin "1") (pinfunction "1_1") (pintype "passive"))
    )
    (net (code "46") (name "/P2L_DATA3") (class "Default")
      (node (ref "IC15") (pin "T9") (pinfunction "P2L_DATA3_T9") (pintype "output"))
      (node (ref "R124") (pin "1") (pinfunction "1_1") (pintype "passive"))
    )
    (net (code "47") (name "/P2L_DATA4") (class "Default")
      (node (ref "IC15") (pin "T8") (pinfunction "P2L_DATA4_T8") (pintype "output"))
      (node (ref "R125") (pin "1") (pinfunction "1_1") (pintype "passive"))
    )
    (net (code "48") (name "/P2L_DATA5") (class "Default")
      (node (ref "IC15") (pin "T7") (pinfunction "P2L_DATA5_T7") (pintype "output"))
      (node (ref "R126") (pin "1") (pinfunction "1_1") (pintype "passive"))
    )
    (net (code "49") (name "/P2L_DATA6") (class "Default")
      (node (ref "IC15") (pin "T6") (pinfunction "P2L_DATA6_T6") (pintype "output"))
      (node (ref "R127") (pin "1") (pinfunction "1_1") (pintype "passive"))
    )
    (net (code "50") (name "/P2L_DATA7") (class "Default")
      (node (ref "IC15") (pin "T5") (pinfunction "P2L_DATA7_T5") (pintype "output"))
      (node (ref "R128") (pin "1") (pinfunction "1_1") (pintype "passive"))
    )
    (net (code "51") (name "/P2L_DATA8") (class "Default")
      (node (ref "IC15") (pin "R13") (pinfunction "P2L_DATA8_R13") (pintype "output"))
      (node (ref "R129") (pin "1") (pinfunction "1_1") (pintype "passive"))
    )
    (net (code "52") (name "/P2L_DATA9") (class "Default")
      (node (ref "IC15") (pin "R12") (pinfunction "P2L_DATA9_R12") (pintype "output"))
      (node (ref "R130") (pin "1") (pinfunction "1_1") (pintype "passive"))
    )
    (net (code "53") (name "/P2L_DATA10") (class "Default")
      (node (ref "IC15") (pin "R11") (pinfunction "P2L_DATA10_R11") (pintype "output"))
      (node (ref "R131") (pin "1") (pinfunction "1_1") (pintype "passive"))
    )
    (net (code "54") (name "/P2L_DATA11") (class "Default")
      (node (ref "IC15") (pin "R9") (pinfunction "P2L_DATA11_R9") (pintype "output"))
      (node (ref "R132") (pin "1") (pinfunction "1_1") (pintype "passive"))
    )
    (net (code "55") (name "/P2L_DATA12") (class "Default")
      (node (ref "IC15") (pin "R6") (pinfunction "P2L_DATA12_R6") (pintype "output"))
      (node (ref "R133") (pin "1") (pinfunction "1_1") (pintype "passive"))
    )
    (net (code "56") (name "/P2L_DATA13") (class "Default")
      (node (ref "IC15") (pin "R5") (pinfunction "P2L_DATA13_R5") (pintype "output"))
      (node (ref "R134") (pin "1") (pinfunction "1_1") (pintype "passive"))
    )
    (net (code "57") (name "/P2L_DATA14") (class "Default")
      (node (ref "IC15") (pin "R4") (pinfunction "P2L_DATA14_R4") (pintype "output"))
      (node (ref "R135") (pin "1") (pinfunction "1_1") (pintype "passive"))
    )
    (net (code "58") (name "/P2L_DATA15") (class "Default")
      (node (ref "IC15") (pin "P5") (pinfunction "P2L_DATA15_P5") (pintype "output"))
      (node (ref "R136") (pin "1") (pinfunction "1_1") (pintype "passive"))
    )
    (net (code "60") (name "/P2L_DFRAME") (class "Default")
      (node (ref "IC15") (pin "R7") (pinfunction "P2L_DFRAME_R7") (pintype "output"))
      (node (ref "R120") (pin "1") (pinfunction "1_1") (pintype "passive"))
    )
    (net (code "61") (name "/P2L_RDY") (class "Default")
      (node (ref "IC15") (pin "P9") (pinfunction "P2L_RDY_P9") (pintype "input"))
      (node (ref "R170") (pin "2") (pinfunction "2_2") (pintype "passive"))
    )
    (net (code "62") (name "/P2L_VALID") (class "Default")
      (node (ref "IC15") (pin "P7") (pinfunction "P2L_VALID_P7") (pintype "output"))
      (node (ref "R119") (pin "1") (pinfunction "1_1") (pintype "passive"))
    )
    (net (code "63") (name "/PECLKIN_N") (class "Default")
      (node (ref "IC15") (pin "H5") (pinfunction "PECLKINn_H5") (pintype "input"))
    )
    (net (code "64") (name "/PECLKIN_P") (class "Default")
      (node (ref "IC15") (pin "G5") (pinfunction "PECLKINp_G5") (pintype "input"))
    )
    (net (code "65") (name "/PER0_N") (class "Default")
      (node (ref "IC15") (pin "A2") (pinfunction "PERn0_A2") (pintype "input"))
    )
    (net (code "66") (name "/PER0_P") (class "Default")
      (node (ref "IC15") (pin "B2") (pinfunction "PERp0_B2") (pintype "input"))
    )
    (net (code "67") (name "/PER1_N") (class "Default")
      (node (ref "IC15") (pin "H1") (pinfunction "PERn1_H1") (pintype "input"))
    )
    (net (code "68") (name "/PER1_P") (class "Default")
      (node (ref "IC15") (pin "G1") (pinfunction "PERp1_G1") (pintype "input"))
    )
    (net (code "69") (name "/PER2_N") (class "Default")
      (node (ref "IC15") (pin "K1") (pinfunction "PERp2_K1") (pintype "input"))
    )
    (net (code "70") (name "/PER2_P") (class "Default")
      (node (ref "IC15") (pin "J1") (pinfunction "PERn2_J1") (pintype "input"))
    )
    (net (code "71") (name "/PER3_N") (class "Default")
      (node (ref "IC15") (pin "T2") (pinfunction "PERn3_T2") (pintype "input"))
    )
    (net (code "72") (name "/PER3_P") (class "Default")
      (node (ref "IC15") (pin "R2") (pinfunction "PERp3_R2") (pintype "input"))
    )
    (net (code "73") (name "/PERST_N") (class "Default")
      (node (ref "R147") (pin "1") (pinfunction "1_1") (pintype "passive"))
    )
    (net (code "74") (name "/PET0_N") (class "Default")
      (node (ref "IC15") (pin "D1") (pinfunction "PETn0_D1") (pintype "output"))
    )
    (net (code "75") (name "/PET0_P") (class "Default")
      (node (ref "IC15") (pin "C1") (pinfunction "PETp0_C1") (pintype "output"))
    )
    (net (code "76") (name "/PET1_N") (class "Default")
      (node (ref "IC15") (pin "E2") (pinfunction "PETn1_E2") (pintype "output"))
    )
    (net (code "77") (name "/PET1_P") (class "Default")
      (node (ref "IC15") (pin "F2") (pinfunction "PETp1_F2") (pintype "output"))
    )
    (net (code "78") (name "/PET2_N") (class "Default")
      (node (ref "IC15") (pin "M2") (pinfunction "PETn2_M2") (pintype "output"))
    )
    (net (code "79") (name "/PET2_P") (class "Default")
      (node (ref "IC15") (pin "L2") (pinfunction "PETp2_L2") (pintype "output"))
    )
    (net (code "80") (name "/PET3_N") (class "Default")
      (node (ref "IC15") (pin "N1") (pinfunction "PETn3_N1") (pintype "output"))
    )
    (net (code "81") (name "/PET3_P") (class "Default")
      (node (ref "IC15") (pin "P1") (pinfunction "PETp3_P1") (pintype "output"))
    )
    (net (code "82") (name "/P_RD_D_RDY0") (class "Default")
      (node (ref "IC15") (pin "M14") (pinfunction "P_RD_D_RDY0_M14") (pintype "output"))
      (node (ref "R223") (pin "2") (pinfunction "2_2") (pintype "passive"))
    )
    (net (code "83") (name "/P_RD_D_RDY1") (class "Default")
      (node (ref "IC15") (pin "L14") (pinfunction "P_RD_D_RDY1_L14") (pintype "output"))
      (node (ref "R222") (pin "2") (pinfunction "2_2") (pintype "passive"))
    )
    (net (code "84") (name "/P_WR_RDY0") (class "Default")
      (node (ref "IC15") (pin "N12") (pinfunction "P_WR_RDY0_N12") (pintype "input"))
      (node (ref "R153") (pin "2") (pinfunction "2_2") (pintype "passive"))
    )
    (net (code "85") (name "/P_WR_RDY1") (class "Default")
      (node (ref "IC15") (pin "N11") (pinfunction "P_WR_RDY1_N11") (pintype "input"))
      (node (ref "R171") (pin "2") (pinfunction "2_2") (pintype "passive"))
    )
    (net (code "86") (name "/P_WR_REQ0") (class "Default")
      (node (ref "IC15") (pin "N9") (pinfunction "P_WR_REQ0_N9") (pintype "output"))
    )
    (net (code "87") (name "/P_WR_REQ1") (class "Default")
      (node (ref "IC15") (pin "P10") (pinfunction "P_WR_REQ1_P10") (pintype "output"))
      (node (ref "R116") (pin "1") (pinfunction "1_1") (pintype "passive"))
    )
    (net (code "88") (name "/RX_ERROR") (class "Default")
      (node (ref "IC15") (pin "N6") (pinfunction "RX_ERROR_N6") (pintype "input"))
      (node (ref "R169") (pin "2") (pinfunction "2_2") (pintype "passive"))
    )
    (net (code "89") (name "/SPRI_CLK") (class "Default")
      (node (ref "IC15") (pin "A8") (pinfunction "SPRI_CLK_A8") (pintype "bidirectional"))
    )
    (net (code "90") (name "/SPRI_CONFIG") (class "Default")
      (node (ref "IC15") (pin "C11") (pinfunction "SPRI_CONFIG_C11") (pintype "bidirectional"))
    )
    (net (code "91") (name "/SPRI_DATAOUT") (class "Default")
      (node (ref "IC15") (pin "B10") (pinfunction "SPRI_DATAOUT_B10") (pintype "bidirectional"))
    )
    (net (code "92") (name "/SPRI_DIN") (class "Default")
      (node (ref "IC15") (pin "B6") (pinfunction "GPIO13_B6") (pintype "bidirectional"))
    )
    (net (code "93") (name "/SPRI_DONE") (class "Default")
      (node (ref "IC15") (pin "A12") (pinfunction "SPRI_DONE_A12") (pintype "bidirectional"))
    )
    (net (code "94") (name "/SPRI_FLASH_CS") (class "Default")
      (node (ref "IC15") (pin "C7") (pinfunction "GPIO12_C7") (pintype "bidirectional"))
    )
    (net (code "95") (name "/SPRI_STATUS") (class "Default")
      (node (ref "IC15") (pin "B14") (pinfunction "SPRI_STATUS_B14") (pintype "bidirectional"))
    )
    (net (code "96") (name "/SPRI_XI_SWAP") (class "Default")
      (node (ref "IC15") (pin "B13") (pinfunction "SPRI_XI_SWAP_B13") (pintype "bidirectional"))
    )
    (net (code "97") (name "/TX_ERROR") (class "Default")
      (node (ref "IC15") (pin "N14") (pinfunction "TX_ERROR_N14") (pintype "output"))
      (node (ref "R220") (pin "2") (pinfunction "2_2") (pintype "passive"))
    )
    (net (code "98") (name "/VC_RDY0") (class "Default")
      (node (ref "IC15") (pin "P12") (pinfunction "VC_RDY0_P12") (pintype "output"))
      (node (ref "R10") (pin "1") (pinfunction "1_1") (pintype "passive"))
    )
    (net (code "99") (name "/VC_RDY1") (class "Default")
      (node (ref "IC15") (pin "P11") (pinfunction "VC_RDY1_P11") (pintype "output"))
      (node (ref "R172") (pin "1") (pinfunction "1_1") (pintype "passive"))
    )
    (net (code "100") (name "GND") (class "Default")
      (node (ref "C24") (pin "1") (pinfunction "1_1") (pintype "passive"))
      (node (ref "C291") (pin "1") (pinfunction "1_1") (pintype "passive"))
      (node (ref "C292") (pin "1") (pinfunction "1_1") (pintype "passive"))
      (node (ref "C293") (pin "1") (pinfunction "1_1") (pintype "passive"))
      (node (ref "C294") (pin "1") (pinfunction "1_1") (pintype "passive"))
      (node (ref "C295") (pin "1") (pinfunction "1_1") (pintype "passive"))
      (node (ref "C296") (pin "1") (pinfunction "1_1") (pintype "passive"))
      (node (ref "C297") (pin "1") (pinfunction "1_1") (pintype "passive"))
      (node (ref "C298") (pin "1") (pinfunction "1_1") (pintype "passive"))
      (node (ref "C299") (pin "1") (pinfunction "1_1") (pintype "passive"))
      (node (ref "C300") (pin "1") (pinfunction "1_1") (pintype "passive"))
      (node (ref "C301") (pin "1") (pinfunction "1_1") (pintype "passive"))
      (node (ref "C302") (pin "1") (pinfunction "1_1") (pintype "passive"))
      (node (ref "IC15") (pin "A4") (pinfunction "DBG0_A4") (pintype "input"))
      (node (ref "IC15") (pin "A5") (pinfunction "DBG7_A5") (pintype "input"))
      (node (ref "IC15") (pin "B4") (pinfunction "DBG2_B4") (pintype "input"))
      (node (ref "IC15") (pin "B5") (pinfunction "DBG6_B5") (pintype "input"))
      (node (ref "IC15") (pin "C5") (pinfunction "DBG5_C5") (pintype "input"))
      (node (ref "IC15") (pin "C6") (pinfunction "DBG1_C6") (pintype "input"))
      (node (ref "IC15") (pin "D6") (pinfunction "SCAN_EN_D6") (pintype "input"))
      (node (ref "IC15") (pin "D7") (pinfunction "DBG3_D7") (pintype "input"))
      (node (ref "IC15") (pin "E6") (pinfunction "TEST_EN_E6") (pintype "input"))
      (node (ref "IC15") (pin "E7") (pinfunction "DBG4_E7") (pintype "input"))
      (node (ref "IC15") (pin "K6") (pinfunction "LCLK_MODE3_K6") (pintype "input"))
      (node (ref "IC15") (pin "L4") (pinfunction "LCLK_MODE2_L4") (pintype "input"))
      (node (ref "IC15") (pin "M4") (pinfunction "LCLK_MODE1_M4") (pintype "input"))
      (node (ref "IC15") (pin "M5") (pinfunction "LCLK_MODE0_M5") (pintype "input"))
      (node (ref "IC16") (pin "1") (pinfunction "A0_1") (pintype "input"))
      (node (ref "IC16") (pin "4") (pinfunction "VSS_4") (pintype "power_in"))
      (node (ref "IC16") (pin "7") (pinfunction "WP_7") (pintype "input"))
      (node (ref "OSC3") (pin "2") (pinfunction "GND_2") (pintype "power_in"))
      (node (ref "R137") (pin "1") (pinfunction "1_1") (pintype "passive"))
      (node (ref "R138") (pin "1") (pinfunction "1_1") (pintype "passive"))
      (node (ref "R151") (pin "1") (pinfunction "1_1") (pintype "passive"))
      (node (ref "R205") (pin "2") (pinfunction "2_2") (pintype "passive"))
      (node (ref "R208") (pin "1") (pinfunction "1_1") (pintype "passive"))
      (node (ref "R212") (pin "1") (pinfunction "1_1") (pintype "passive"))
      (node (ref "SW1") (pin "1") (pinfunction "1_1") (pintype "bidirectional"))
      (node (ref "W1") (pin "2") (pinfunction "2_2") (pintype "bidirectional"))
    )
    (net (code "101") (name "Net-(IC15C-LB_REF_CLK_MI)") (class "Default")
      (node (ref "IC15") (pin "D12") (pinfunction "LB_REF_CLK_MI_D12") (pintype "input"))
      (node (ref "OSC3") (pin "3") (pinfunction "OUT_3") (pintype "output"))
    )
    (net (code "102") (name "Net-(IC15C-LB_REF_CLK_MO)") (class "Default")
      (node (ref "IC15") (pin "C13") (pinfunction "LB_REF_CLK_MO_C13") (pintype "output"))
      (node (ref "R212") (pin "2") (pinfunction "2_2") (pintype "passive"))
    )
    (net (code "103") (name "Net-(IC15E-TCK)") (class "Default")
      (node (ref "IC15") (pin "F11") (pinfunction "TCK_F11") (pintype "input"))
      (node (ref "R233") (pin "1") (pinfunction "1_1") (pintype "passive"))
    )
    (net (code "104") (name "Net-(IC15E-TDI)") (class "Default")
      (node (ref "IC15") (pin "A9") (pinfunction "TDI_A9") (pintype "input"))
      (node (ref "R98") (pin "1") (pinfunction "1_1") (pintype "passive"))
    )
    (net (code "105") (name "Net-(IC15E-TDO)") (class "Default")
      (node (ref "IC15") (pin "A14") (pinfunction "TDO_A14") (pintype "output"))
      (node (ref "R206") (pin "1") (pinfunction "1_1") (pintype "passive"))
    )
    (net (code "106") (name "Net-(IC15E-TMS)") (class "Default")
      (node (ref "IC15") (pin "F10") (pinfunction "TMS_F10") (pintype "input"))
      (node (ref "R232") (pin "1") (pinfunction "1_1") (pintype "passive"))
    )
    (net (code "107") (name "Net-(IC15E-TRST)") (class "Default")
      (node (ref "IC15") (pin "B12") (pinfunction "TRST_B12") (pintype "input"))
      (node (ref "R205") (pin "1") (pinfunction "1_1") (pintype "passive"))
    )
    (net (code "108") (name "Net-(IC15F-RSTIN)") (class "Default")
      (node (ref "IC15") (pin "B8") (pinfunction "RSTIN_B8") (pintype "input"))
      (node (ref "R147") (pin "2") (pinfunction "2_2") (pintype "passive"))
      (node (ref "R208") (pin "2") (pinfunction "2_2") (pintype "passive"))
    )
    (net (code "109") (name "Net-(IC15H-EEPROM_EN)") (class "Default")
      (node (ref "IC15") (pin "E5") (pinfunction "EEPROM_EN_E5") (pintype "input"))
      (node (ref "R196") (pin "1") (pinfunction "1_1") (pintype "passive"))
    )
    (net (code "110") (name "Net-(IC15I-GPIO6)") (class "Default")
      (node (ref "IC15") (pin "A11") (pinfunction "GPIO6_A11") (pintype "bidirectional"))
      (node (ref "TP8") (pin "1") (pinfunction "1_1") (pintype "bidirectional"))
    )
    (net (code "111") (name "Net-(IC15I-GPIO7)") (class "Default")
      (node (ref "IC15") (pin "A10") (pinfunction "GPIO7_A10") (pintype "bidirectional"))
      (node (ref "TP7") (pin "1") (pinfunction "1_1") (pintype "bidirectional"))
    )
    (net (code "112") (name "Net-(IC15I-GPIO10)") (class "Default")
      (node (ref "IC15") (pin "C8") (pinfunction "GPIO10_C8") (pintype "bidirectional"))
      (node (ref "TP6") (pin "1") (pinfunction "1_1") (pintype "bidirectional"))
    )
    (net (code "113") (name "Net-(IC15I-GPIO11)") (class "Default")
      (node (ref "IC15") (pin "F7") (pinfunction "GPIO11_F7") (pintype "bidirectional"))
      (node (ref "TP5") (pin "1") (pinfunction "1_1") (pintype "bidirectional"))
    )
    (net (code "114") (name "P3V3") (class "Default")
      (node (ref "C291") (pin "2") (pinfunction "2_2") (pintype "passive"))
      (node (ref "IC16") (pin "2") (pinfunction "A1_2") (pintype "input"))
      (node (ref "IC16") (pin "3") (pinfunction "A2_3") (pintype "input"))
      (node (ref "IC16") (pin "8") (pinfunction "VCC_8") (pintype "power_in"))
      (node (ref "OSC3") (pin "1") (pinfunction "OE_1") (pintype "input"))
      (node (ref "OSC3") (pin "4") (pinfunction "VDD_4") (pintype "power_in"))
      (node (ref "R196") (pin "2") (pinfunction "2_2") (pintype "passive"))
      (node (ref "R198") (pin "2") (pinfunction "2_2") (pintype "passive"))
      (node (ref "R199") (pin "2") (pinfunction "2_2") (pintype "passive"))
      (node (ref "R206") (pin "2") (pinfunction "2_2") (pintype "passive"))
      (node (ref "R232") (pin "2") (pinfunction "2_2") (pintype "passive"))
      (node (ref "R233") (pin "2") (pinfunction "2_2") (pintype "passive"))
      (node (ref "R98") (pin "2") (pinfunction "2_2") (pintype "passive"))
    )
    (net (code "115") (name "VTT_GN4124") (class "Default")
      (node (ref "C24") (pin "2") (pinfunction "2_2") (pintype "passive"))
      (node (ref "C292") (pin "2") (pinfunction "2_2") (pintype "passive"))
      (node (ref "C293") (pin "2") (pinfunction "2_2") (pintype "passive"))
      (node (ref "C294") (pin "2") (pinfunction "2_2") (pintype "passive"))
      (node (ref "C295") (pin "2") (pinfunction "2_2") (pintype "passive"))
      (node (ref "C296") (pin "2") (pinfunction "2_2") (pintype "passive"))
      (node (ref "C297") (pin "2") (pinfunction "2_2") (pintype "passive"))
      (node (ref "C298") (pin "2") (pinfunction "2_2") (pintype "passive"))
      (node (ref "C299") (pin "2") (pinfunction "2_2") (pintype "passive"))
      (node (ref "C300") (pin "2") (pinfunction "2_2") (pintype "passive"))
      (node (ref "C301") (pin "2") (pinfunction "2_2") (pintype "passive"))
      (node (ref "C302") (pin "2") (pinfunction "2_2") (pintype "passive"))
      (node (ref "R10") (pin "2") (pinfunction "2_2") (pintype "passive"))
      (node (ref "R116") (pin "2") (pinfunction "2_2") (pintype "passive"))
      (node (ref "R117") (pin "2") (pinfunction "2_2") (pintype "passive"))
      (node (ref "R118") (pin "2") (pinfunction "2_2") (pintype "passive"))
      (node (ref "R119") (pin "2") (pinfunction "2_2") (pintype "passive"))
      (node (ref "R120") (pin "2") (pinfunction "2_2") (pintype "passive"))
      (node (ref "R121") (pin "2") (pinfunction "2_2") (pintype "passive"))
      (node (ref "R122") (pin "2") (pinfunction "2_2") (pintype "passive"))
      (node (ref "R123") (pin "2") (pinfunction "2_2") (pintype "passive"))
      (node (ref "R124") (pin "2") (pinfunction "2_2") (pintype "passive"))
      (node (ref "R125") (pin "2") (pinfunction "2_2") (pintype "passive"))
      (node (ref "R126") (pin "2") (pinfunction "2_2") (pintype "passive"))
      (node (ref "R127") (pin "2") (pinfunction "2_2") (pintype "passive"))
      (node (ref "R128") (pin "2") (pinfunction "2_2") (pintype "passive"))
      (node (ref "R129") (pin "2") (pinfunction "2_2") (pintype "passive"))
      (node (ref "R130") (pin "2") (pinfunction "2_2") (pintype "passive"))
      (node (ref "R131") (pin "2") (pinfunction "2_2") (pintype "passive"))
      (node (ref "R132") (pin "2") (pinfunction "2_2") (pintype "passive"))
      (node (ref "R133") (pin "2") (pinfunction "2_2") (pintype "passive"))
      (node (ref "R134") (pin "2") (pinfunction "2_2") (pintype "passive"))
      (node (ref "R135") (pin "2") (pinfunction "2_2") (pintype "passive"))
      (node (ref "R136") (pin "2") (pinfunction "2_2") (pintype "passive"))
      (node (ref "R153") (pin "1") (pinfunction "1_1") (pintype "passive"))
      (node (ref "R154") (pin "2") (pinfunction "2_2") (pintype "passive"))
      (node (ref "R156") (pin "2") (pinfunction "2_2") (pintype "passive"))
      (node (ref "R157") (pin "2") (pinfunction "2_2") (pintype "passive"))
      (node (ref "R158") (pin "2") (pinfunction "2_2") (pintype "passive"))
      (node (ref "R159") (pin "2") (pinfunction "2_2") (pintype "passive"))
      (node (ref "R160") (pin "2") (pinfunction "2_2") (pintype "passive"))
      (node (ref "R161") (pin "2") (pinfunction "2_2") (pintype "passive"))
      (node (ref "R162") (pin "2") (pinfunction "2_2") (pintype "passive"))
      (node (ref "R169") (pin "1") (pinfunction "1_1") (pintype "passive"))
      (node (ref "R170") (pin "1") (pinfunction "1_1") (pintype "passive"))
      (node (ref "R171") (pin "1") (pinfunction "1_1") (pintype "passive"))
      (node (ref "R172") (pin "2") (pinfunction "2_2") (pintype "passive"))
      (node (ref "R173") (pin "2") (pinfunction "2_2") (pintype "passive"))
      (node (ref "R174") (pin "2") (pinfunction "2_2") (pintype "passive"))
      (node (ref "R175") (pin "2") (pinfunction "2_2") (pintype "passive"))
      (node (ref "R176") (pin "2") (pinfunction "2_2") (pintype "passive"))
      (node (ref "R177") (pin "2") (pinfunction "2_2") (pintype "passive"))
      (node (ref "R178") (pin "2") (pinfunction "2_2") (pintype "passive"))
      (node (ref "R179") (pin "2") (pinfunction "2_2") (pintype "passive"))
      (node (ref "R180") (pin "2") (pinfunction "2_2") (pintype "passive"))
      (node (ref "R181") (pin "2") (pinfunction "2_2") (pintype "passive"))
      (node (ref "R182") (pin "2") (pinfunction "2_2") (pintype "passive"))
      (node (ref "R183") (pin "2") (pinfunction "2_2") (pintype "passive"))
      (node (ref "R184") (pin "2") (pinfunction "2_2") (pintype "passive"))
      (node (ref "R185") (pin "2") (pinfunction "2_2") (pintype "passive"))
      (node (ref "R220") (pin "1") (pinfunction "1_1") (pintype "passive"))
      (node (ref "R221") (pin "1") (pinfunction "1_1") (pintype "passive"))
      (node (ref "R222") (pin "1") (pinfunction "1_1") (pintype "passive"))
      (node (ref "R223") (pin "1") (pinfunction "1_1") (pintype "passive"))
      (node (ref "R224") (pin "1") (pinfunction "1_1") (pintype "passive"))
      (node (ref "R225") (pin "1") (pinfunction "1_1") (pintype "passive"))
    )
    (net (code "116") (name "unconnected-(IC15F-RSTOUT33-PadC9)") (class "Default")
      (node (ref "IC15") (pin "C9") (pinfunction "RSTOUT33_C9") (pintype "output+no_connect"))
    )
    (net (code "117") (name "unconnected-(IC15J-PLL_TEST_OUT-PadA15)") (class "Default")
      (node (ref "IC15") (pin "A15") (pinfunction "PLL_TEST_OUT_A15") (pintype "bidirectional+no_connect"))
    )
  )
)
